# Wireless_Receiver.net
KiCad netlist of a schematic drawn in Altium Designer
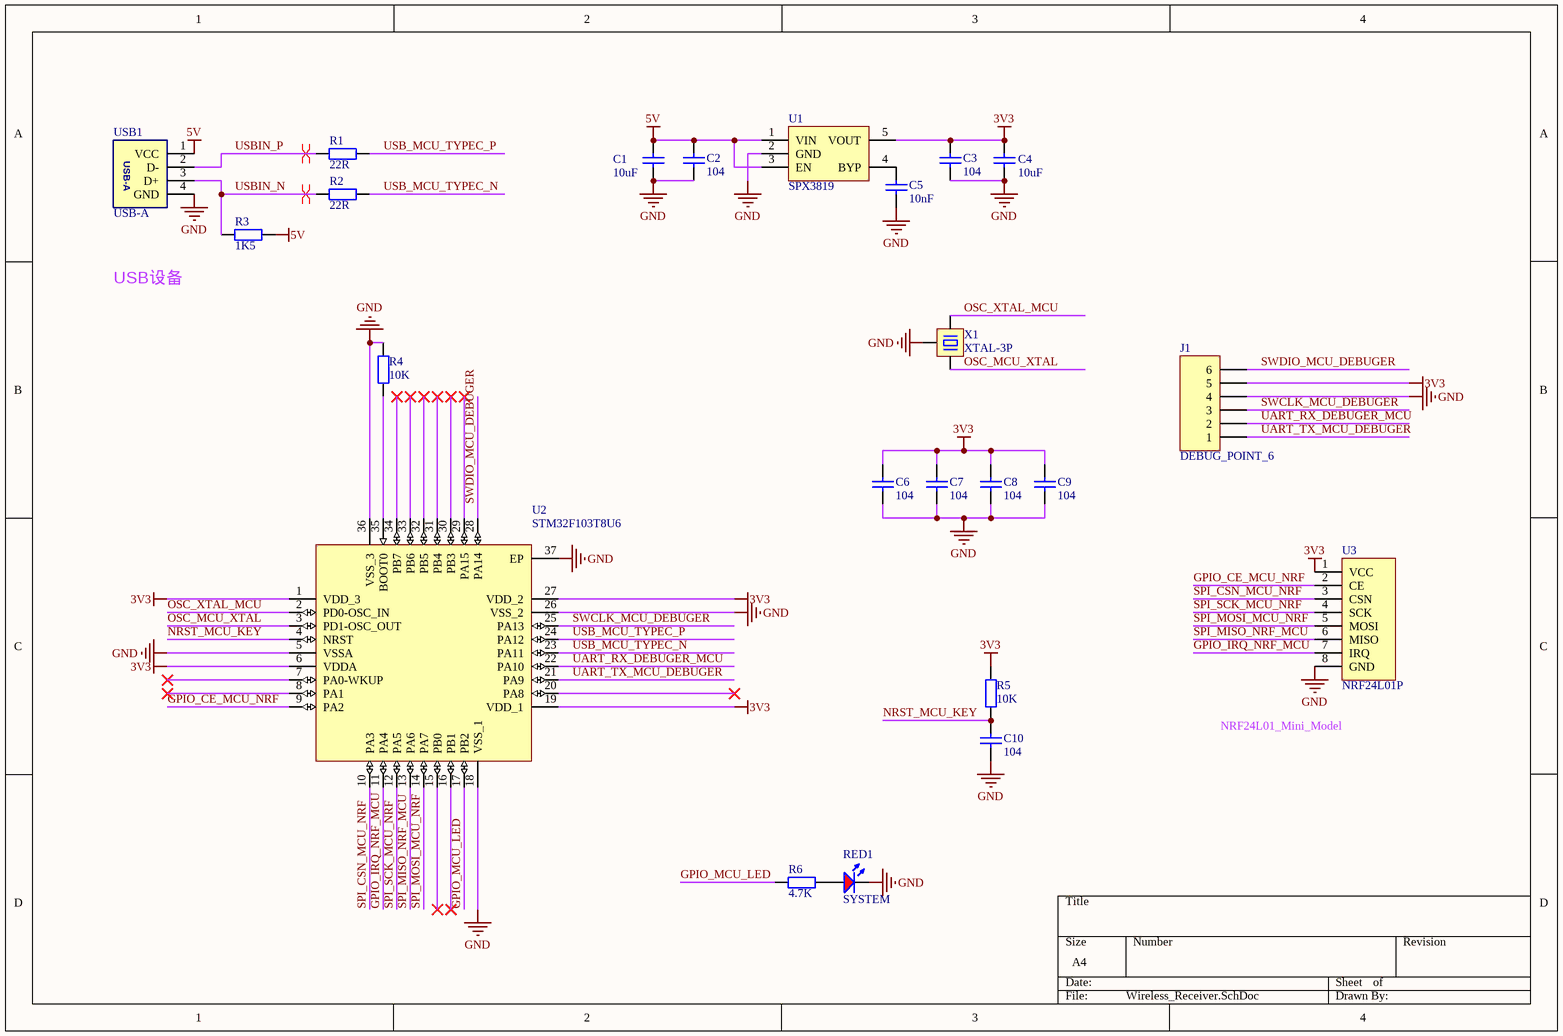
[diagram p0: Wireless_Receiver.SchDoc]

(export (version "E")
  (design (tool "Eeschema 10.0.6"))
  (components
    (comp (ref "C1")
      (value "10uF")
      (footprint "Cap-0603-M")
      (description "贴片陶瓷电容")
      (libsource (lib "Miscellaneous Base") (part "CAP"))
    )
    (comp (ref "C2")
      (value "104")
      (footprint "Cap-0402-M")
      (description "贴片陶瓷电容")
      (libsource (lib "Miscellaneous Base") (part "CAP"))
    )
    (comp (ref "C3")
      (value "104")
      (footprint "Cap-0402-M")
      (description "贴片陶瓷电容")
      (libsource (lib "Miscellaneous Base") (part "CAP"))
    )
    (comp (ref "C4")
      (value "10uF")
      (footprint "Cap-0603-M")
      (description "贴片陶瓷电容")
      (libsource (lib "Miscellaneous Base") (part "CAP"))
    )
    (comp (ref "C5")
      (value "10nF")
      (footprint "Cap-0402-M")
      (description "贴片陶瓷电容")
      (libsource (lib "Miscellaneous Base") (part "CAP"))
    )
    (comp (ref "C6")
      (value "104")
      (footprint "Cap-0402-M")
      (description "贴片陶瓷电容")
      (libsource (lib "Miscellaneous Base") (part "CAP"))
    )
    (comp (ref "C7")
      (value "104")
      (footprint "Cap-0402-M")
      (description "贴片陶瓷电容")
      (libsource (lib "Miscellaneous Base") (part "CAP"))
    )
    (comp (ref "C8")
      (value "104")
      (footprint "Cap-0402-M")
      (description "贴片陶瓷电容")
      (libsource (lib "Miscellaneous Base") (part "CAP"))
    )
    (comp (ref "C9")
      (value "104")
      (footprint "Cap-0402-M")
      (description "贴片陶瓷电容")
      (libsource (lib "Miscellaneous Base") (part "CAP"))
    )
    (comp (ref "C10")
      (value "104")
      (footprint "Cap-0402-M")
      (description "贴片陶瓷电容")
      (libsource (lib "Miscellaneous Base") (part "CAP"))
    )
    (comp (ref "J1")
      (value "DEBUG_POINT_6")
      (footprint "DEBUG_POINT_6")
      (libsource (lib "Miscellaneous Others") (part "DEBUG_POINT_6"))
    )
    (comp (ref "R1")
      (value "22R")
      (footprint "Res-0402-M")
      (description "贴片电阻")
      (libsource (lib "Miscellaneous Base") (part "RES"))
    )
    (comp (ref "R2")
      (value "22R")
      (footprint "Res-0402-M")
      (description "贴片电阻")
      (libsource (lib "Miscellaneous Base") (part "RES"))
    )
    (comp (ref "R3")
      (value "1K5")
      (footprint "Res-0402-M")
      (description "贴片电阻")
      (libsource (lib "Miscellaneous Base") (part "RES"))
    )
    (comp (ref "R4")
      (value "10K")
      (footprint "Res-0402-M")
      (description "贴片电阻")
      (libsource (lib "") (part "RES_1"))
    )
    (comp (ref "R5")
      (value "10K")
      (footprint "Res-0402-M")
      (description "贴片电阻")
      (libsource (lib "") (part "RES_1"))
    )
    (comp (ref "R6")
      (value "4.7K")
      (footprint "Res-0402-M")
      (description "贴片电阻")
      (libsource (lib "") (part "RES_2"))
    )
    (comp (ref "RED1")
      (value "SYSTEM")
      (footprint "LED_0603_R")
      (description "发光二极管")
      (libsource (lib "Miscellaneous Transistor") (part "LED_SMD_RED"))
    )
    (comp (ref "U1")
      (value "SPX3819")
      (footprint "SOT23-5")
      (libsource (lib "Miscellaneous PMIC") (part "SPX3819"))
    )
    (comp (ref "U2")
      (value "STM32F103T8U6")
      (footprint "STM-VFQFPN36_L _2")
      (libsource (lib "Miscellaneous MCU") (part "STM32F103T8U6"))
    )
    (comp (ref "U3")
      (value "NRF24L01P")
      (footprint "NRF24L01P")
      (description "2.4G无线模块")
      (libsource (lib "Miscellaneous Model") (part "NRF24L01P"))
    )
    (comp (ref "USB1")
      (value "USB-A")
      (footprint "USB_A/P_B")
      (libsource (lib "Miscellaneous Socket") (part "USB-A"))
    )
    (comp (ref "X1")
      (value "XTAL-3P")
      (footprint "OSC 3213-3P")
      (description "3脚无源晶振带电容")
      (libsource (lib "Miscellaneous XTAL") (part "XTAL-3P"))
    )
  )
  (nets
    (net (code "1") (name "/GPIO_CE_MCU_NRF") (class "Default")
      (node (ref "U2") (pin "9") (pinfunction "PA2_9") (pintype "bidirectional"))
      (node (ref "U3") (pin "2") (pinfunction "CE_2") (pintype "power_in"))
    )
    (net (code "2") (name "/GPIO_IRQ_NRF_MCU") (class "Default")
      (node (ref "U2") (pin "11") (pinfunction "PA4_11") (pintype "bidirectional"))
      (node (ref "U3") (pin "7") (pinfunction "IRQ_7") (pintype "power_in"))
    )
    (net (code "3") (name "/GPIO_MCU_LED") (class "Default")
      (node (ref "R6") (pin "2") (pinfunction "2_2") (pintype "passive"))
      (node (ref "U2") (pin "17") (pinfunction "PB2_17") (pintype "bidirectional"))
    )
    (net (code "4") (name "/NRST_MCU_KEY") (class "Default")
      (node (ref "C10") (pin "2") (pinfunction "2_2") (pintype "passive"))
      (node (ref "R5") (pin "1") (pinfunction "1_1") (pintype "passive"))
      (node (ref "U2") (pin "4") (pinfunction "NRST_4") (pintype "bidirectional"))
    )
    (net (code "5") (name "/OSC_MCU_XTAL") (class "Default")
      (node (ref "U2") (pin "3") (pinfunction "PD1-OSC_OUT_3") (pintype "bidirectional"))
      (node (ref "X1") (pin "3") (pinfunction "3_3") (pintype "passive"))
    )
    (net (code "6") (name "/OSC_XTAL_MCU") (class "Default")
      (node (ref "U2") (pin "2") (pinfunction "PD0-OSC_IN_2") (pintype "bidirectional"))
      (node (ref "X1") (pin "1") (pinfunction "1_1") (pintype "passive"))
    )
    (net (code "7") (name "/SPI_CSN_MCU_NRF") (class "Default")
      (node (ref "U2") (pin "10") (pinfunction "PA3_10") (pintype "bidirectional"))
      (node (ref "U3") (pin "3") (pinfunction "CSN_3") (pintype "power_in"))
    )
    (net (code "8") (name "/SPI_MISO_NRF_MCU") (class "Default")
      (node (ref "U2") (pin "13") (pinfunction "PA6_13") (pintype "bidirectional"))
      (node (ref "U3") (pin "6") (pinfunction "MISO_6") (pintype "power_in"))
    )
    (net (code "9") (name "/SPI_MOSI_MCU_NRF") (class "Default")
      (node (ref "U2") (pin "14") (pinfunction "PA7_14") (pintype "bidirectional"))
      (node (ref "U3") (pin "5") (pinfunction "MOSI_5") (pintype "power_in"))
    )
    (net (code "10") (name "/SPI_SCK_MCU_NRF") (class "Default")
      (node (ref "U2") (pin "12") (pinfunction "PA5_12") (pintype "bidirectional"))
      (node (ref "U3") (pin "4") (pinfunction "SCK_4") (pintype "power_in"))
    )
    (net (code "11") (name "/SWCLK_MCU_DEBUGER") (class "Default")
      (node (ref "J1") (pin "3") (pinfunction "3_3") (pintype "passive"))
      (node (ref "U2") (pin "25") (pinfunction "PA13_25") (pintype "bidirectional"))
    )
    (net (code "12") (name "/SWDIO_MCU_DEBUGER") (class "Default")
      (node (ref "J1") (pin "6") (pinfunction "6_6") (pintype "passive"))
      (node (ref "U2") (pin "28") (pinfunction "PA14_28") (pintype "bidirectional"))
    )
    (net (code "13") (name "/UART_RX_DEBUGER_MCU") (class "Default")
      (node (ref "J1") (pin "2") (pinfunction "2_2") (pintype "passive"))
      (node (ref "U2") (pin "22") (pinfunction "PA10_22") (pintype "bidirectional"))
    )
    (net (code "14") (name "/UART_TX_MCU_DEBUGER") (class "Default")
      (node (ref "J1") (pin "1") (pinfunction "1_1") (pintype "passive"))
      (node (ref "U2") (pin "21") (pinfunction "PA9_21") (pintype "bidirectional"))
    )
    (net (code "15") (name "/USBIN_N") (class "Default")
      (node (ref "R2") (pin "1") (pinfunction "1_1") (pintype "passive"))
      (node (ref "R3") (pin "1") (pinfunction "1_1") (pintype "passive"))
      (node (ref "USB1") (pin "3") (pinfunction "D+_3") (pintype "passive"))
    )
    (net (code "16") (name "/USBIN_P") (class "Default")
      (node (ref "R1") (pin "1") (pinfunction "1_1") (pintype "passive"))
      (node (ref "USB1") (pin "2") (pinfunction "D-_2") (pintype "passive"))
    )
    (net (code "17") (name "/USB_MCU_TYPEC_N") (class "Default")
      (node (ref "R2") (pin "2") (pinfunction "2_2") (pintype "passive"))
      (node (ref "U2") (pin "23") (pinfunction "PA11_23") (pintype "bidirectional"))
    )
    (net (code "18") (name "/USB_MCU_TYPEC_P") (class "Default")
      (node (ref "R1") (pin "2") (pinfunction "2_2") (pintype "passive"))
      (node (ref "U2") (pin "24") (pinfunction "PA12_24") (pintype "bidirectional"))
    )
    (net (code "19") (name "3V3") (class "Default")
      (node (ref "C3") (pin "2") (pinfunction "2_2") (pintype "passive"))
      (node (ref "C4") (pin "2") (pinfunction "2_2") (pintype "passive"))
      (node (ref "C6") (pin "2") (pinfunction "2_2") (pintype "passive"))
      (node (ref "C7") (pin "2") (pinfunction "2_2") (pintype "passive"))
      (node (ref "C8") (pin "2") (pinfunction "2_2") (pintype "passive"))
      (node (ref "C9") (pin "2") (pinfunction "2_2") (pintype "passive"))
      (node (ref "J1") (pin "5") (pinfunction "5_5") (pintype "passive"))
      (node (ref "R5") (pin "2") (pinfunction "2_2") (pintype "passive"))
      (node (ref "U1") (pin "5") (pinfunction "VOUT_5") (pintype "power_in"))
      (node (ref "U2") (pin "1") (pinfunction "VDD_3_1") (pintype "power_in"))
      (node (ref "U2") (pin "19") (pinfunction "VDD_1_19") (pintype "power_in"))
      (node (ref "U2") (pin "27") (pinfunction "VDD_2_27") (pintype "power_in"))
      (node (ref "U2") (pin "6") (pinfunction "VDDA_6") (pintype "power_in"))
      (node (ref "U3") (pin "1") (pinfunction "VCC_1") (pintype "power_in"))
    )
    (net (code "20") (name "5V") (class "Default")
      (node (ref "C1") (pin "2") (pinfunction "2_2") (pintype "passive"))
      (node (ref "C2") (pin "2") (pinfunction "2_2") (pintype "passive"))
      (node (ref "R3") (pin "2") (pinfunction "2_2") (pintype "passive"))
      (node (ref "U1") (pin "1") (pinfunction "VIN_1") (pintype "power_in"))
      (node (ref "U1") (pin "3") (pinfunction "EN_3") (pintype "power_in"))
      (node (ref "USB1") (pin "1") (pinfunction "VCC_1") (pintype "passive"))
    )
    (net (code "21") (name "GND") (class "Default")
      (node (ref "C1") (pin "1") (pinfunction "1_1") (pintype "passive"))
      (node (ref "C10") (pin "1") (pinfunction "1_1") (pintype "passive"))
      (node (ref "C2") (pin "1") (pinfunction "1_1") (pintype "passive"))
      (node (ref "C3") (pin "1") (pinfunction "1_1") (pintype "passive"))
      (node (ref "C4") (pin "1") (pinfunction "1_1") (pintype "passive"))
      (node (ref "C5") (pin "1") (pinfunction "1_1") (pintype "passive"))
      (node (ref "C6") (pin "1") (pinfunction "1_1") (pintype "passive"))
      (node (ref "C7") (pin "1") (pinfunction "1_1") (pintype "passive"))
      (node (ref "C8") (pin "1") (pinfunction "1_1") (pintype "passive"))
      (node (ref "C9") (pin "1") (pinfunction "1_1") (pintype "passive"))
      (node (ref "J1") (pin "4") (pinfunction "4_4") (pintype "passive"))
      (node (ref "R4") (pin "2") (pinfunction "2_2") (pintype "passive"))
      (node (ref "RED1") (pin "2") (pinfunction "K_2") (pintype "passive"))
      (node (ref "U1") (pin "2") (pinfunction "GND_2") (pintype "power_in"))
      (node (ref "U2") (pin "18") (pinfunction "VSS_1_18") (pintype "power_in"))
      (node (ref "U2") (pin "26") (pinfunction "VSS_2_26") (pintype "power_in"))
      (node (ref "U2") (pin "36") (pinfunction "VSS_3_36") (pintype "power_in"))
      (node (ref "U2") (pin "37") (pinfunction "EP_37") (pintype "power_in"))
      (node (ref "U2") (pin "5") (pinfunction "VSSA_5") (pintype "power_in"))
      (node (ref "U3") (pin "8") (pinfunction "GND_8") (pintype "power_in"))
      (node (ref "USB1") (pin "4") (pinfunction "GND_4") (pintype "passive"))
      (node (ref "X1") (pin "2") (pinfunction "2_2") (pintype "passive"))
    )
    (net (code "22") (name "Net-(RED1-A)") (class "Default")
      (node (ref "R6") (pin "1") (pinfunction "1_1") (pintype "passive"))
      (node (ref "RED1") (pin "1") (pinfunction "A_1") (pintype "passive"))
    )
    (net (code "23") (name "Net-(U1-BYP)") (class "Default")
      (node (ref "C5") (pin "2") (pinfunction "2_2") (pintype "passive"))
      (node (ref "U1") (pin "4") (pinfunction "BYP_4") (pintype "power_in"))
    )
    (net (code "24") (name "Net-(U2-BOOT0)") (class "Default")
      (node (ref "R4") (pin "1") (pinfunction "1_1") (pintype "passive"))
      (node (ref "U2") (pin "35") (pinfunction "BOOT0_35") (pintype "input"))
    )
    (net (code "25") (name "unconnected-(U2-PA0-WKUP-Pad7)") (class "Default")
      (node (ref "U2") (pin "7") (pinfunction "PA0-WKUP_7") (pintype "bidirectional+no_connect"))
    )
    (net (code "26") (name "unconnected-(U2-PA1-Pad8)") (class "Default")
      (node (ref "U2") (pin "8") (pinfunction "PA1_8") (pintype "bidirectional+no_connect"))
    )
    (net (code "27") (name "unconnected-(U2-PA8-Pad20)") (class "Default")
      (node (ref "U2") (pin "20") (pinfunction "PA8_20") (pintype "bidirectional+no_connect"))
    )
    (net (code "28") (name "unconnected-(U2-PA15-Pad29)") (class "Default")
      (node (ref "U2") (pin "29") (pinfunction "PA15_29") (pintype "bidirectional+no_connect"))
    )
    (net (code "29") (name "unconnected-(U2-PB0-Pad15)") (class "Default")
      (node (ref "U2") (pin "15") (pinfunction "PB0_15") (pintype "bidirectional+no_connect"))
    )
    (net (code "30") (name "unconnected-(U2-PB1-Pad16)") (class "Default")
      (node (ref "U2") (pin "16") (pinfunction "PB1_16") (pintype "bidirectional+no_connect"))
    )
    (net (code "31") (name "unconnected-(U2-PB3-Pad30)") (class "Default")
      (node (ref "U2") (pin "30") (pinfunction "PB3_30") (pintype "bidirectional+no_connect"))
    )
    (net (code "32") (name "unconnected-(U2-PB4-Pad31)") (class "Default")
      (node (ref "U2") (pin "31") (pinfunction "PB4_31") (pintype "bidirectional+no_connect"))
    )
    (net (code "33") (name "unconnected-(U2-PB5-Pad32)") (class "Default")
      (node (ref "U2") (pin "32") (pinfunction "PB5_32") (pintype "bidirectional+no_connect"))
    )
    (net (code "34") (name "unconnected-(U2-PB6-Pad33)") (class "Default")
      (node (ref "U2") (pin "33") (pinfunction "PB6_33") (pintype "bidirectional+no_connect"))
    )
    (net (code "35") (name "unconnected-(U2-PB7-Pad34)") (class "Default")
      (node (ref "U2") (pin "34") (pinfunction "PB7_34") (pintype "bidirectional+no_connect"))
    )
  )
)
